# FTDI.net
KiCad netlist of a schematic drawn in Altium Designer
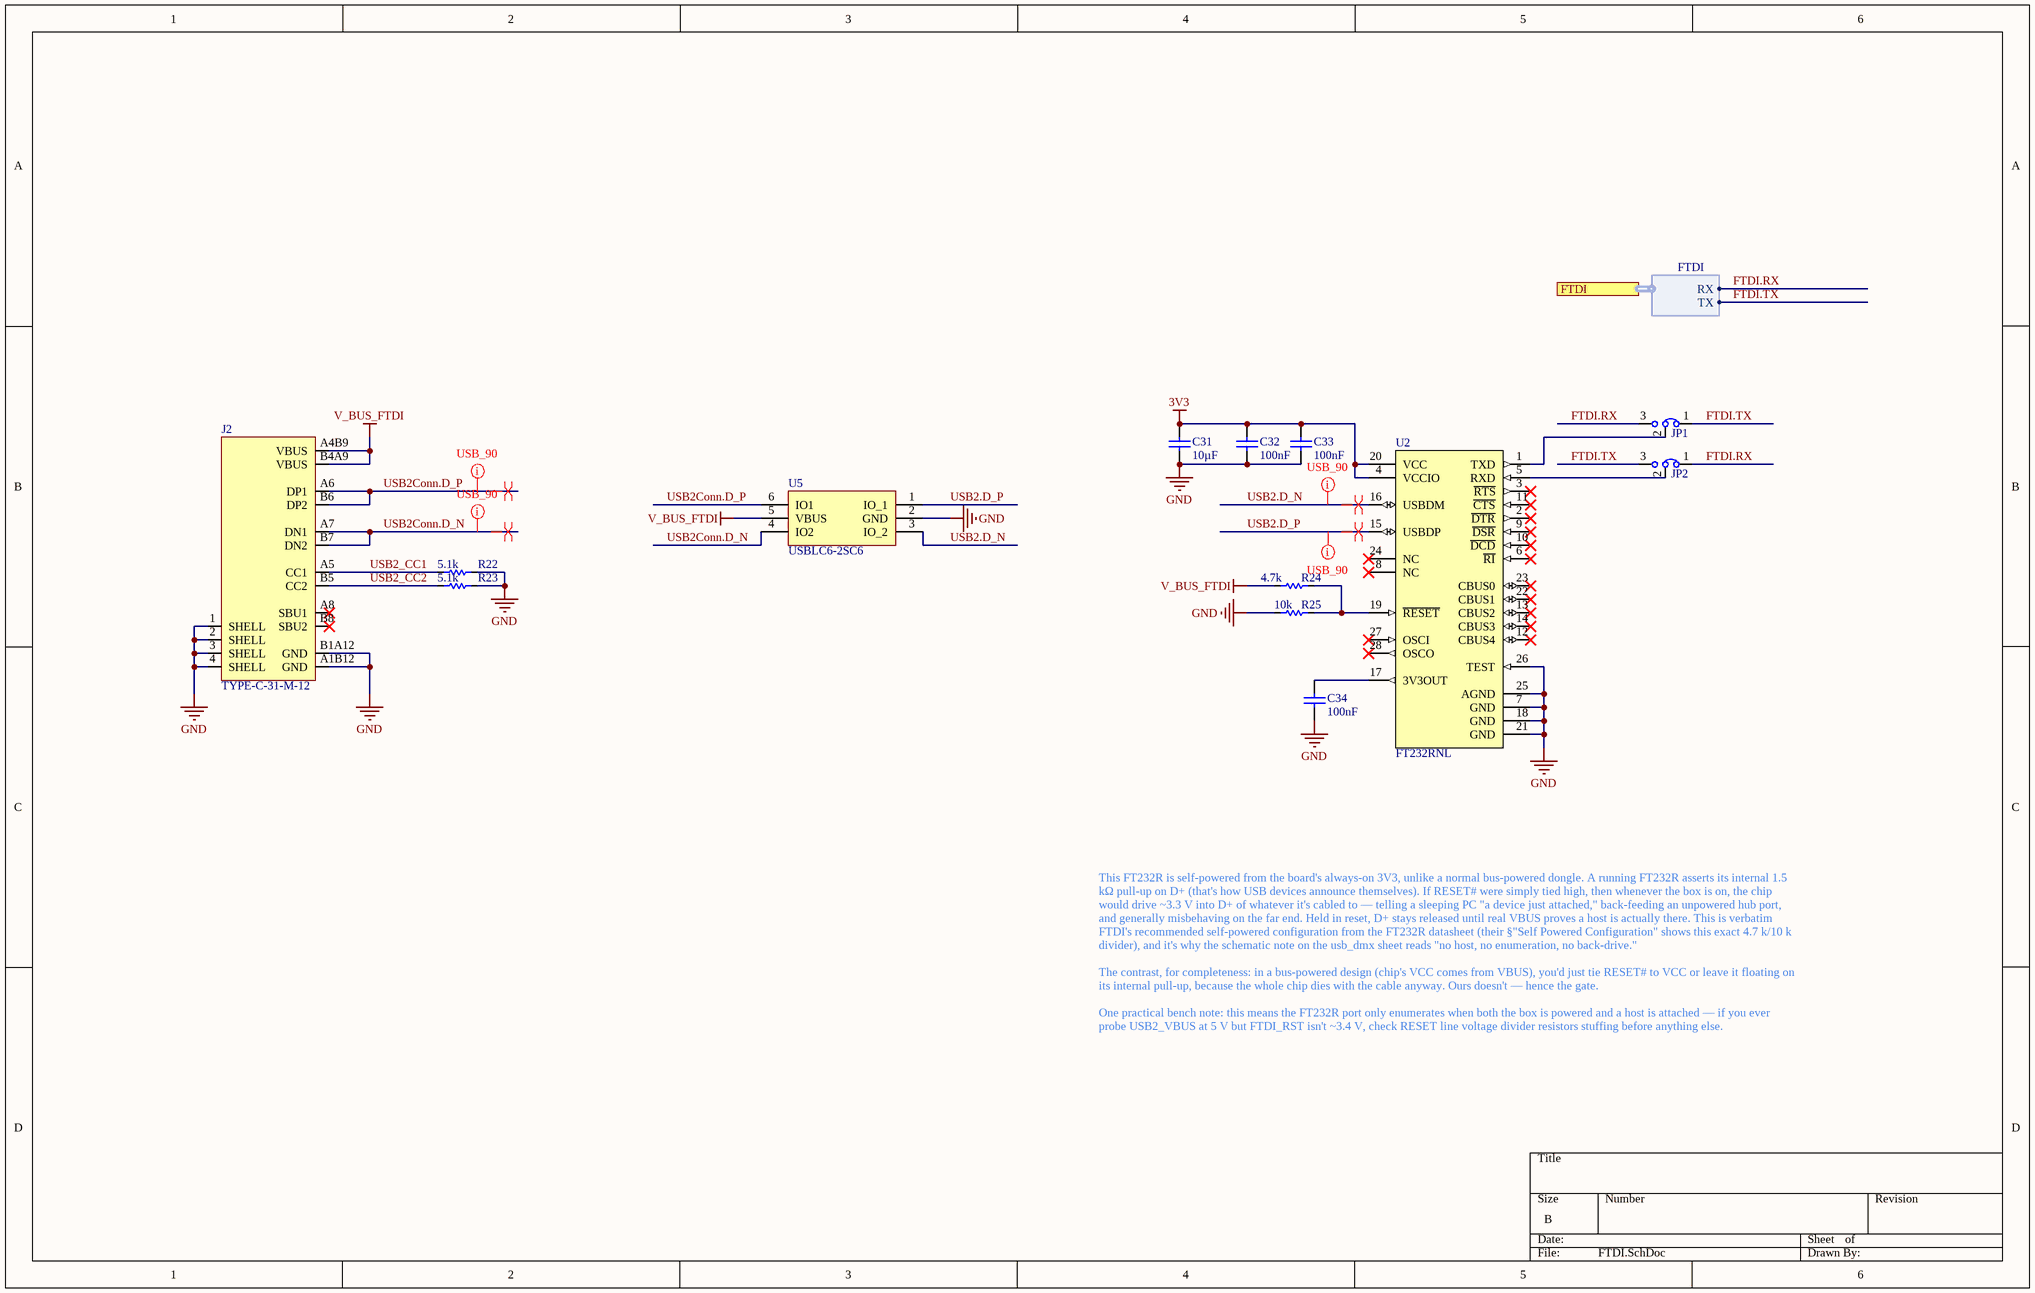
[diagram p0: FTDI.SchDoc]

(export (version "E")
  (design (tool "Eeschema 10.0.6"))
  (components
    (comp (ref "C31")
      (value "10µF")
      (footprint "CAPC2012X14N_0805_MED")
      (description "Ceramic Capacitor, Multilayer, Ceramic, 10uF, 16V, 10%, X6S, 0805")
      (fields (field (name "TOLERANCE") "10%") (field (name "Comment") "GRM21BC81C106KA73L"))
      (libsource (lib "Equus Computer Systems") (part "CAP-NP-2"))
    )
    (comp (ref "C32")
      (value "100nF")
      (footprint "CAPC1608X10N_0603_MED")
      (fields (field (name "Comment") "CC0603KRX7R0BB104"))
      (libsource (lib "Equus Computer Systems") (part "CAP-NP-2"))
    )
    (comp (ref "C33")
      (value "100nF")
      (footprint "CAPC1608X10N_0603_MED")
      (fields (field (name "Comment") "CC0603KRX7R0BB104"))
      (libsource (lib "Equus Computer Systems") (part "CAP-NP-2"))
    )
    (comp (ref "C34")
      (value "100nF")
      (footprint "CAPC1608X10N_0603_MED")
      (fields (field (name "Comment") "CC0603KRX7R0BB104"))
      (libsource (lib "Equus Computer Systems") (part "CAP-NP-2"))
    )
    (comp (ref "J2")
      (value "TYPE-C-31-M-12")
      (footprint "Type-C-31-M-12")
      (description "20V USB C 2.0 16P Female header")
      (libsource (lib "Equus Computer Systems") (part "USB C 2.0"))
    )
    (comp (ref "JP1")
      (value "Jumper 3 x 1 Bridge 1-2 Solder Bridge")
      (footprint "Jumper 3 Solder Bridge 1-2 0603")
      (description "0603 Solder Bridge Jumper Surface Mount")
      (fields (field (name "TOLERANCE") "1%"))
      (libsource (lib "Equus Computer Systems") (part "Jumper 3 Bridge 12"))
    )
    (comp (ref "JP2")
      (value "Jumper 3 x 1 Bridge 1-2 Solder Bridge")
      (footprint "Jumper 3 Solder Bridge 1-2 0603")
      (description "0603 Solder Bridge Jumper Surface Mount")
      (fields (field (name "TOLERANCE") "1%"))
      (libsource (lib "Equus Computer Systems") (part "Jumper 3 Bridge 12"))
    )
    (comp (ref "R22")
      (value "5.1k")
      (footprint "RESC1608X06N_0603_MED")
      (fields
        (field (name "POWER") "100mW")
        (field (name "TOLERANCE") "1%")
        (field (name "Comment") "RC0603FR-075K1L")
      )
      (libsource (lib "Equus Computer Systems") (part "RES-2"))
    )
    (comp (ref "R23")
      (value "5.1k")
      (footprint "RESC1608X06N_0603_MED")
      (fields
        (field (name "POWER") "100mW")
        (field (name "TOLERANCE") "1%")
        (field (name "Comment") "RC0603FR-075K1L")
      )
      (libsource (lib "Equus Computer Systems") (part "RES-2"))
    )
    (comp (ref "R24")
      (value "4.7k")
      (footprint "RESC1608X06N_0603_MED")
      (fields
        (field (name "TOLERANCE") "1%")
        (field (name "POWER") "100mW")
        (field (name "Comment") "RC0603FR-074K7L")
      )
      (libsource (lib "Equus Computer Systems") (part "RES-2"))
    )
    (comp (ref "R25")
      (value "10k")
      (footprint "RESC1608X06N_0603_MED")
      (fields
        (field (name "POWER") "100mW")
        (field (name "TOLERANCE") "1%")
        (field (name "Comment") "RC0603FR-1010KL")
      )
      (libsource (lib "Equus Computer Systems") (part "RES-2"))
    )
    (comp (ref "U2")
      (value "FT232RNL")
      (footprint "FP-FT232RNL-REEL-MFG")
      (description "Integrated Circuit Interface USB-UART; RS-232; 12Mbs; 3.3-5.25V; -40+85 deg.C; SMD; SSOP28")
      (libsource (lib "Equus Computer Systems") (part "FT232RL"))
    )
    (comp (ref "U5")
      (value "USBLC6-2SC6")
      (footprint "ESD_SOT23-6L")
      (description "Very low capacitance ESD protection")
      (fields (field (name "MANUFACTURER") "STMICROELECTRONICS"))
      (libsource (lib "Equus Computer Systems") (part "USBLC6-2SC6"))
    )
  )
  (nets
    (net (code "2") (name "/FTDI.RX") (class "Default")
      (node (ref "JP1") (pin "3") (pinfunction "3_3") (pintype "passive"))
      (node (ref "JP2") (pin "1") (pinfunction "1_1") (pintype "passive"))
    )
    (net (code "3") (name "/FTDI.TX") (class "Default")
      (node (ref "JP1") (pin "1") (pinfunction "1_1") (pintype "passive"))
      (node (ref "JP2") (pin "3") (pinfunction "3_3") (pintype "passive"))
    )
    (net (code "4") (name "/USB2.D_N") (class "Default")
      (node (ref "U2") (pin "16") (pinfunction "USBDM_16") (pintype "bidirectional"))
      (node (ref "U5") (pin "3") (pinfunction "IO_2_3") (pintype "passive"))
    )
    (net (code "5") (name "/USB2.D_P") (class "Default")
      (node (ref "U2") (pin "15") (pinfunction "USBDP_15") (pintype "bidirectional"))
      (node (ref "U5") (pin "1") (pinfunction "IO_1_1") (pintype "passive"))
    )
    (net (code "6") (name "/USB2Conn.D_N") (class "Default")
      (node (ref "J2") (pin "A7") (pinfunction "DN1_A7") (pintype "passive"))
      (node (ref "J2") (pin "B7") (pinfunction "DN2_B7") (pintype "passive"))
      (node (ref "U5") (pin "4") (pinfunction "IO2_4") (pintype "passive"))
    )
    (net (code "7") (name "/USB2Conn.D_P") (class "Default")
      (node (ref "J2") (pin "A6") (pinfunction "DP1_A6") (pintype "passive"))
      (node (ref "J2") (pin "B6") (pinfunction "DP2_B6") (pintype "passive"))
      (node (ref "U5") (pin "6") (pinfunction "IO1_6") (pintype "passive"))
    )
    (net (code "8") (name "/USB2_CC1") (class "Default")
      (node (ref "J2") (pin "A5") (pinfunction "CC1_A5") (pintype "passive"))
      (node (ref "R22") (pin "1") (pinfunction "1_1") (pintype "passive"))
    )
    (net (code "9") (name "/USB2_CC2") (class "Default")
      (node (ref "J2") (pin "B5") (pinfunction "CC2_B5") (pintype "passive"))
      (node (ref "R23") (pin "1") (pinfunction "1_1") (pintype "passive"))
    )
    (net (code "11") (name "3V3") (class "Default")
      (node (ref "C31") (pin "2") (pinfunction "2_2") (pintype "passive"))
      (node (ref "C32") (pin "1") (pinfunction "1_1") (pintype "passive"))
      (node (ref "C33") (pin "1") (pinfunction "1_1") (pintype "passive"))
      (node (ref "U2") (pin "20") (pinfunction "VCC_20") (pintype "power_in"))
      (node (ref "U2") (pin "4") (pinfunction "VCCIO_4") (pintype "power_in"))
    )
    (net (code "12") (name "GND") (class "Default")
      (node (ref "C31") (pin "1") (pinfunction "1_1") (pintype "passive"))
      (node (ref "C32") (pin "2") (pinfunction "2_2") (pintype "passive"))
      (node (ref "C33") (pin "2") (pinfunction "2_2") (pintype "passive"))
      (node (ref "C34") (pin "2") (pinfunction "2_2") (pintype "passive"))
      (node (ref "J2") (pin "1") (pinfunction "SHELL_1") (pintype "passive"))
      (node (ref "J2") (pin "2") (pinfunction "SHELL_2") (pintype "passive"))
      (node (ref "J2") (pin "3") (pinfunction "SHELL_3") (pintype "passive"))
      (node (ref "J2") (pin "4") (pinfunction "SHELL_4") (pintype "passive"))
      (node (ref "J2") (pin "A1B12") (pinfunction "GND_A1B12") (pintype "passive"))
      (node (ref "J2") (pin "B1A12") (pinfunction "GND_B1A12") (pintype "passive"))
      (node (ref "R22") (pin "2") (pinfunction "2_2") (pintype "passive"))
      (node (ref "R23") (pin "2") (pinfunction "2_2") (pintype "passive"))
      (node (ref "R25") (pin "1") (pinfunction "1_1") (pintype "passive"))
      (node (ref "U2") (pin "18") (pinfunction "GND_18") (pintype "power_in"))
      (node (ref "U2") (pin "21") (pinfunction "GND_21") (pintype "power_in"))
      (node (ref "U2") (pin "25") (pinfunction "AGND_25") (pintype "power_in"))
      (node (ref "U2") (pin "26") (pinfunction "TEST_26") (pintype "input"))
      (node (ref "U2") (pin "7") (pinfunction "GND_7") (pintype "power_in"))
      (node (ref "U5") (pin "2") (pinfunction "GND_2") (pintype "passive"))
    )
    (net (code "13") (name "Net-(U2-3V3OUT)") (class "Default")
      (node (ref "C34") (pin "1") (pinfunction "1_1") (pintype "passive"))
      (node (ref "U2") (pin "17") (pinfunction "3V3OUT_17") (pintype "output"))
    )
    (net (code "14") (name "Net-(U2-RXD)") (class "Default")
      (node (ref "JP2") (pin "2") (pinfunction "2_2") (pintype "passive"))
      (node (ref "U2") (pin "5") (pinfunction "RXD_5") (pintype "input"))
    )
    (net (code "15") (name "Net-(U2-TXD)") (class "Default")
      (node (ref "JP1") (pin "2") (pinfunction "2_2") (pintype "passive"))
      (node (ref "U2") (pin "1") (pinfunction "TXD_1") (pintype "output"))
    )
    (net (code "16") (name "Net-(U2-~{RESET})") (class "Default")
      (node (ref "R24") (pin "1") (pinfunction "1_1") (pintype "passive"))
      (node (ref "R25") (pin "2") (pinfunction "2_2") (pintype "passive"))
      (node (ref "U2") (pin "19") (pinfunction "~{RESET}_19") (pintype "input"))
    )
    (net (code "17") (name "V_BUS_FTDI") (class "Default")
      (node (ref "J2") (pin "A4B9") (pinfunction "VBUS_A4B9") (pintype "passive"))
      (node (ref "J2") (pin "B4A9") (pinfunction "VBUS_B4A9") (pintype "passive"))
      (node (ref "R24") (pin "2") (pinfunction "2_2") (pintype "passive"))
      (node (ref "U5") (pin "5") (pinfunction "VBUS_5") (pintype "passive"))
    )
    (net (code "18") (name "unconnected-(J2-SBU1-PadA8)") (class "Default")
      (node (ref "J2") (pin "A8") (pinfunction "SBU1_A8") (pintype "passive+no_connect"))
    )
    (net (code "19") (name "unconnected-(J2-SBU2-PadB8)") (class "Default")
      (node (ref "J2") (pin "B8") (pinfunction "SBU2_B8") (pintype "passive+no_connect"))
    )
    (net (code "20") (name "unconnected-(U2-CBUS0-Pad23)") (class "Default")
      (node (ref "U2") (pin "23") (pinfunction "CBUS0_23") (pintype "bidirectional+no_connect"))
    )
    (net (code "21") (name "unconnected-(U2-CBUS1-Pad22)") (class "Default")
      (node (ref "U2") (pin "22") (pinfunction "CBUS1_22") (pintype "bidirectional+no_connect"))
    )
    (net (code "22") (name "unconnected-(U2-CBUS2-Pad13)") (class "Default")
      (node (ref "U2") (pin "13") (pinfunction "CBUS2_13") (pintype "bidirectional+no_connect"))
    )
    (net (code "23") (name "unconnected-(U2-CBUS3-Pad14)") (class "Default")
      (node (ref "U2") (pin "14") (pinfunction "CBUS3_14") (pintype "bidirectional+no_connect"))
    )
    (net (code "24") (name "unconnected-(U2-CBUS4-Pad12)") (class "Default")
      (node (ref "U2") (pin "12") (pinfunction "CBUS4_12") (pintype "bidirectional+no_connect"))
    )
    (net (code "25") (name "unconnected-(U2-NC-Pad8)") (class "Default")
      (node (ref "U2") (pin "8") (pinfunction "NC_8") (pintype "passive+no_connect"))
    )
    (net (code "26") (name "unconnected-(U2-NC-Pad24)") (class "Default")
      (node (ref "U2") (pin "24") (pinfunction "NC_24") (pintype "passive+no_connect"))
    )
    (net (code "27") (name "unconnected-(U2-OSCI-Pad27)") (class "Default")
      (node (ref "U2") (pin "27") (pinfunction "OSCI_27") (pintype "input+no_connect"))
    )
    (net (code "28") (name "unconnected-(U2-OSCO-Pad28)") (class "Default")
      (node (ref "U2") (pin "28") (pinfunction "OSCO_28") (pintype "output+no_connect"))
    )
    (net (code "29") (name "unconnected-(U2-~{CTS}-Pad11)") (class "Default")
      (node (ref "U2") (pin "11") (pinfunction "~{CTS}_11") (pintype "input+no_connect"))
    )
    (net (code "30") (name "unconnected-(U2-~{DCD}-Pad10)") (class "Default")
      (node (ref "U2") (pin "10") (pinfunction "~{DCD}_10") (pintype "input+no_connect"))
    )
    (net (code "31") (name "unconnected-(U2-~{DSR}-Pad9)") (class "Default")
      (node (ref "U2") (pin "9") (pinfunction "~{DSR}_9") (pintype "input+no_connect"))
    )
    (net (code "32") (name "unconnected-(U2-~{DTR}-Pad2)") (class "Default")
      (node (ref "U2") (pin "2") (pinfunction "~{DTR}_2") (pintype "output+no_connect"))
    )
    (net (code "33") (name "unconnected-(U2-~{RI}-Pad6)") (class "Default")
      (node (ref "U2") (pin "6") (pinfunction "~{RI}_6") (pintype "input+no_connect"))
    )
    (net (code "34") (name "unconnected-(U2-~{RTS}-Pad3)") (class "Default")
      (node (ref "U2") (pin "3") (pinfunction "~{RTS}_3") (pintype "output+no_connect"))
    )
  )
)
